# design.net
KiCad netlist of a schematic drawn in Altium Designer
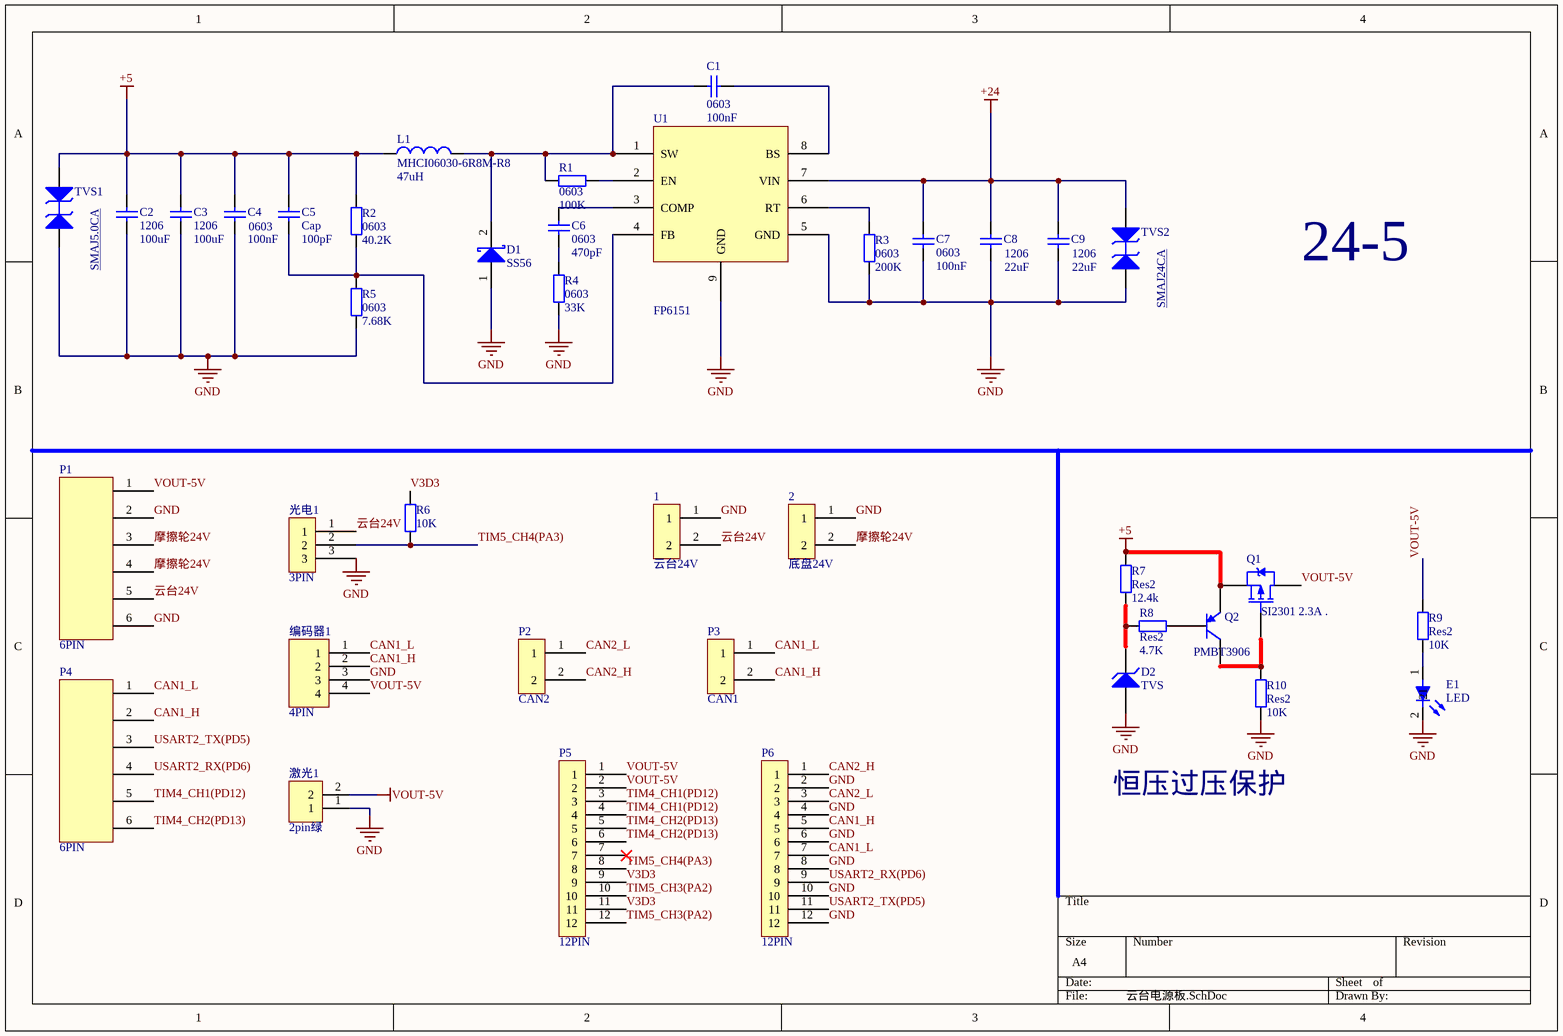
[diagram p0: 云台电源板.SchDoc]

(export (version "E")
  (design (tool "Eeschema 10.0.6"))
  (components
    (comp (ref "1") (value "云台24V") (footprint "XT30 pw") (libsource (lib "PP_SCHlib_Altium") (part "2PIN")))
    (comp (ref "2") (value "底盘24V") (footprint "XT30 pw") (libsource (lib "PP_SCHlib_Altium") (part "2PIN")))
    (comp (ref "C1")
      (value "0603")
      (footprint "C0603")
      (description "Capacitor")
      (fields (field (name "0603") "100nF") (field (name "PUBLISHER") "Altium Limited"))
      (libsource (lib "Miscellaneous Devices") (part "Cap"))
    )
    (comp (ref "C2")
      (value "1206")
      (footprint "C1206")
      (description "Capacitor")
      (fields (field (name "ALTIUM_VALUE") "100uF") (field (name "PUBLISHER") "Altium Limited"))
      (libsource (lib "Miscellaneous Devices") (part "Cap"))
    )
    (comp (ref "C3")
      (value "1206")
      (footprint "C1206")
      (description "Capacitor")
      (fields (field (name "ALTIUM_VALUE") "100uF") (field (name "PUBLISHER") "Altium Limited"))
      (libsource (lib "Miscellaneous Devices") (part "Cap"))
    )
    (comp (ref "C4")
      (value "0603")
      (footprint "C0603")
      (description "Capacitor")
      (fields (field (name "ALTIUM_VALUE") "100nF") (field (name "PUBLISHER") "Altium Limited"))
      (libsource (lib "Miscellaneous Devices") (part "Cap"))
    )
    (comp (ref "C5")
      (value "Cap")
      (footprint "C0603")
      (description "Capacitor")
      (fields (field (name "ALTIUM_VALUE") "100pF") (field (name "PUBLISHER") "Altium Limited"))
      (libsource (lib "Miscellaneous Devices") (part "Cap"))
    )
    (comp (ref "C6")
      (value "0603")
      (footprint "C0603")
      (description "Capacitor")
      (fields (field (name "ALTIUM_VALUE") "470pF") (field (name "PUBLISHER") "Altium Limited"))
      (libsource (lib "Miscellaneous Devices") (part "Cap"))
    )
    (comp (ref "C7")
      (value "0603")
      (footprint "C0603")
      (description "Capacitor")
      (fields (field (name "0603") "100nF") (field (name "PUBLISHER") "Altium Limited"))
      (libsource (lib "Miscellaneous Devices") (part "Cap"))
    )
    (comp (ref "C8")
      (value "1206")
      (footprint "C1206")
      (description "Capacitor")
      (fields (field (name "ALTIUM_VALUE") "22uF") (field (name "PUBLISHER") "Altium Limited"))
      (libsource (lib "Miscellaneous Devices") (part "Cap"))
    )
    (comp (ref "C9")
      (value "1206")
      (footprint "C1206")
      (description "Capacitor")
      (fields (field (name "ALTIUM_VALUE") "22uF") (field (name "PUBLISHER") "Altium Limited"))
      (libsource (lib "Miscellaneous Devices") (part "Cap"))
    )
    (comp (ref "D1")
      (value "D-Schottky")
      (footprint "SS56")
      (description "肖特基二极管")
      (fields (field (name "TYPE") "SS56") (field (name "PUBLISHER") "Altium Limited"))
      (libsource (lib "更多原理图库") (part "D-Schottky"))
    )
    (comp (ref "D2")
      (value "TVS")
      (footprint "SMA")
      (description "Zener Diode")
      (fields (field (name "PUBLISHER") "Altium Limited"))
      (libsource (lib "Miscellaneous Devices") (part "D Zener"))
    )
    (comp (ref "E1")
      (value "LED")
      (footprint "LED0805")
      (description "Typical RED, GREEN, YELLOW, AMBER GaAs LED")
      (fields (field (name "PUBLISHER") "Altium Limited"))
      (libsource (lib "PP_SCHlib_Altium") (part "LED"))
    )
    (comp (ref "L1")
      (value "MHCI06030-6R8M-R8")
      (footprint "L")
      (description "Inductor")
      (fields (field (name "ALTIUM_VALUE") "47uH") (field (name "PUBLISHER") "Altium Limited"))
      (libsource (lib "Miscellaneous Devices") (part "Inductor"))
    )
    (comp (ref "P1")
      (value "6PIN")
      (footprint "43045-6P-L")
      (libsource (lib "PP_SCHlib_Altium") (part "6PIN"))
    )
    (comp (ref "P2")
      (value "CAN2")
      (footprint "XH2.54-2-W")
      (libsource (lib "PP_SCHlib_Altium") (part "2PIN"))
    )
    (comp (ref "P3")
      (value "CAN1")
      (footprint "XH2.54-2-W")
      (libsource (lib "PP_SCHlib_Altium") (part "2PIN"))
    )
    (comp (ref "P4")
      (value "6PIN")
      (footprint "43045-6P-L")
      (libsource (lib "PP_SCHlib_Altium") (part "6PIN"))
    )
    (comp (ref "P5") (value "12PIN") (footprint "2mm-2-12") (libsource (lib "更多原理图库") (part "12PIN")))
    (comp (ref "P6") (value "12PIN") (footprint "2mm-2-12") (libsource (lib "更多原理图库") (part "12PIN")))
    (comp (ref "Q1")
      (value "SI2301 2.3A .")
      (footprint "SOT23")
      (description "P-Channel Power MOSFET")
      (fields (field (name "PUBLISHER") "Altium Limited"))
      (libsource (lib "Miscellaneous Devices") (part "PMOS-2"))
    )
    (comp (ref "Q2")
      (value "PMBT3906")
      (footprint "SOT23")
      (description "PNP Bipolar Transistor")
      (fields (field (name "PUBLISHER") "Altium Limited"))
      (libsource (lib "Miscellaneous Devices") (part "PNP"))
    )
    (comp (ref "R1")
      (value "0603")
      (footprint "R0603")
      (description "Resistor")
      (fields (field (name "0603") "100K") (field (name "PUBLISHER") "Altium Limited"))
      (libsource (lib "") (part "Res2_2"))
    )
    (comp (ref "R2")
      (value "0603")
      (footprint "R0603")
      (description "Resistor")
      (fields (field (name "ALTIUM_VALUE") "40.2K") (field (name "PUBLISHER") "Altium Limited"))
      (libsource (lib "Miscellaneous Devices") (part "Res2"))
    )
    (comp (ref "R3")
      (value "0603")
      (footprint "R0603")
      (description "Resistor")
      (fields (field (name "0603") "200K") (field (name "PUBLISHER") "Altium Limited"))
      (libsource (lib "Miscellaneous Devices") (part "Res2"))
    )
    (comp (ref "R4")
      (value "0603")
      (footprint "R0603")
      (description "Resistor")
      (fields (field (name "ALTIUM_VALUE") "33K") (field (name "PUBLISHER") "Altium Limited"))
      (libsource (lib "Miscellaneous Devices") (part "Res2"))
    )
    (comp (ref "R5")
      (value "0603")
      (footprint "R0603")
      (description "Resistor")
      (fields (field (name "ALTIUM_VALUE") "7.68K") (field (name "PUBLISHER") "Altium Limited"))
      (libsource (lib "Miscellaneous Devices") (part "Res2"))
    )
    (comp (ref "R6")
      (value "10K")
      (footprint "R0805")
      (description "贴片电阻")
      (fields (field (name "Comment") "Res1") (field (name "PUBLISHER") "Altium Limited"))
      (libsource (lib "stm32test") (part "Res1"))
    )
    (comp (ref "R7")
      (value "Res2")
      (footprint "0603(偏大)")
      (description "Resistor")
      (fields (field (name "ALTIUM_VALUE") "12.4k") (field (name "PUBLISHER") "Altium Limited"))
      (libsource (lib "Miscellaneous Devices") (part "Res2"))
    )
    (comp (ref "R8")
      (value "Res2")
      (footprint "0603(偏大)")
      (description "Resistor")
      (fields (field (name "ALTIUM_VALUE") "4.7K") (field (name "PUBLISHER") "Altium Limited"))
      (libsource (lib "") (part "Res2_1"))
    )
    (comp (ref "R9")
      (value "Res2")
      (footprint "0603(偏大)")
      (description "Resistor")
      (fields (field (name "ALTIUM_VALUE") "10K") (field (name "PUBLISHER") "Altium Limited"))
      (libsource (lib "") (part "Res2_3"))
    )
    (comp (ref "R10")
      (value "Res2")
      (footprint "0603(偏大)")
      (description "Resistor")
      (fields (field (name "ALTIUM_VALUE") "10K") (field (name "PUBLISHER") "Altium Limited"))
      (libsource (lib "Miscellaneous Devices") (part "Res2"))
    )
    (comp (ref "TVS1")
      (value "SMAJ5.0CA")
      (footprint "SMAJ")
      (libsource (lib "VL53L0X激光测距传感器模块") (part "TVS"))
    )
    (comp (ref "TVS2")
      (value "SMAJ24CA")
      (footprint "SMAJ")
      (libsource (lib "VL53L0X激光测距传感器模块") (part "TVS"))
    )
    (comp (ref "U1") (value "FP6151") (footprint "FP6151") (libsource (lib "Schlib1") (part "FP6151")))
    (comp (ref "光电1")
      (value "3PIN")
      (footprint "GH1.25 3PIN")
      (libsource (lib "PP_SCHlib_Altium") (part "3PIN"))
    )
    (comp (ref "激光1")
      (value "2pin绿")
      (footprint "532610271")
      (description "Molex-53261-0871")
      (fields (field (name "PUBLISHER") "Altium Limited"))
      (libsource (lib "通用板") (part "Molex-53398-0271"))
    )
    (comp (ref "编码器1")
      (value "4PIN")
      (footprint "XH2.54-4-w")
      (libsource (lib "PP_SCHlib_Altium") (part "4PIN"))
    )
  )
  (nets
    (net (code "1") (name "+5") (class "Default")
      (node (ref "C2") (pin "2") (pinfunction "2_2") (pintype "passive"))
      (node (ref "C3") (pin "2") (pinfunction "2_2") (pintype "passive"))
      (node (ref "C4") (pin "2") (pinfunction "2_2") (pintype "passive"))
      (node (ref "C5") (pin "2") (pinfunction "2_2") (pintype "passive"))
      (node (ref "L1") (pin "1") (pinfunction "1_1") (pintype "passive"))
      (node (ref "Q1") (pin "2") (pinfunction "s_2") (pintype "passive"))
      (node (ref "Q2") (pin "2") (pinfunction "2_2") (pintype "passive"))
      (node (ref "R2") (pin "2") (pinfunction "2_2") (pintype "passive"))
      (node (ref "R7") (pin "2") (pinfunction "2_2") (pintype "passive"))
      (node (ref "TVS1") (pin "2") (pinfunction "K_2") (pintype "passive"))
    )
    (net (code "2") (name "+24") (class "Default")
      (node (ref "C7") (pin "2") (pinfunction "2_2") (pintype "passive"))
      (node (ref "C8") (pin "2") (pinfunction "2_2") (pintype "passive"))
      (node (ref "C9") (pin "2") (pinfunction "2_2") (pintype "passive"))
      (node (ref "TVS2") (pin "2") (pinfunction "K_2") (pintype "passive"))
      (node (ref "U1") (pin "7") (pinfunction "VIN_7") (pintype "passive"))
    )
    (net (code "3") (name "/CAN1_H") (class "Default")
      (node (ref "P3") (pin "2") (pinfunction "2_2") (pintype "passive"))
      (node (ref "P4") (pin "2") (pinfunction "2_2") (pintype "passive"))
      (node (ref "P6") (pin "5") (pinfunction "5_5") (pintype "passive"))
      (node (ref "编码器1") (pin "2") (pinfunction "2_2") (pintype "passive"))
    )
    (net (code "4") (name "/CAN1_L") (class "Default")
      (node (ref "P3") (pin "1") (pinfunction "1_1") (pintype "passive"))
      (node (ref "P4") (pin "1") (pinfunction "1_1") (pintype "passive"))
      (node (ref "P6") (pin "7") (pinfunction "7_7") (pintype "passive"))
      (node (ref "编码器1") (pin "1") (pinfunction "1_1") (pintype "passive"))
    )
    (net (code "5") (name "/CAN2_H") (class "Default")
      (node (ref "P2") (pin "2") (pinfunction "2_2") (pintype "passive"))
      (node (ref "P6") (pin "1") (pinfunction "1_1") (pintype "passive"))
    )
    (net (code "6") (name "/CAN2_L") (class "Default")
      (node (ref "P2") (pin "1") (pinfunction "1_1") (pintype "passive"))
      (node (ref "P6") (pin "3") (pinfunction "3_3") (pintype "passive"))
    )
    (net (code "7") (name "/TIM4_CH1(PD12)") (class "Default")
      (node (ref "P4") (pin "5") (pinfunction "5_5") (pintype "passive"))
      (node (ref "P5") (pin "3") (pinfunction "3_3") (pintype "passive"))
      (node (ref "P5") (pin "4") (pinfunction "4_4") (pintype "passive"))
    )
    (net (code "8") (name "/TIM4_CH2(PD13)") (class "Default")
      (node (ref "P4") (pin "6") (pinfunction "6_6") (pintype "passive"))
      (node (ref "P5") (pin "5") (pinfunction "5_5") (pintype "passive"))
      (node (ref "P5") (pin "6") (pinfunction "6_6") (pintype "passive"))
    )
    (net (code "9") (name "/TIM5_CH3(PA2)") (class "Default")
      (node (ref "P5") (pin "10") (pinfunction "10_10") (pintype "passive"))
      (node (ref "P5") (pin "12") (pinfunction "12_12") (pintype "passive"))
    )
    (net (code "10") (name "/TIM5_CH4(PA3)") (class "Default")
      (node (ref "P5") (pin "8") (pinfunction "8_8") (pintype "passive"))
      (node (ref "R6") (pin "1") (pinfunction "1_1") (pintype "passive"))
      (node (ref "光电1") (pin "2") (pinfunction "2_2") (pintype "passive"))
    )
    (net (code "11") (name "/USART2_RX(PD6)") (class "Default")
      (node (ref "P4") (pin "4") (pinfunction "4_4") (pintype "passive"))
      (node (ref "P6") (pin "9") (pinfunction "9_9") (pintype "passive"))
    )
    (net (code "12") (name "/USART2_TX(PD5)") (class "Default")
      (node (ref "P4") (pin "3") (pinfunction "3_3") (pintype "passive"))
      (node (ref "P6") (pin "11") (pinfunction "11_11") (pintype "passive"))
    )
    (net (code "13") (name "/V3D3") (class "Default")
      (node (ref "P5") (pin "11") (pinfunction "11_11") (pintype "passive"))
      (node (ref "P5") (pin "9") (pinfunction "9_9") (pintype "passive"))
      (node (ref "R6") (pin "2") (pinfunction "2_2") (pintype "passive"))
    )
    (net (code "14") (name "/云台24V") (class "Default")
      (node (ref "1") (pin "2") (pinfunction "2_2") (pintype "passive"))
      (node (ref "P1") (pin "5") (pinfunction "5_5") (pintype "passive"))
      (node (ref "光电1") (pin "1") (pinfunction "1_1") (pintype "passive"))
    )
    (net (code "15") (name "/摩擦轮24V") (class "Default")
      (node (ref "2") (pin "2") (pinfunction "2_2") (pintype "passive"))
      (node (ref "P1") (pin "3") (pinfunction "3_3") (pintype "passive"))
      (node (ref "P1") (pin "4") (pinfunction "4_4") (pintype "passive"))
    )
    (net (code "16") (name "GND") (class "Default")
      (node (ref "1") (pin "1") (pinfunction "1_1") (pintype "passive"))
      (node (ref "2") (pin "1") (pinfunction "1_1") (pintype "passive"))
      (node (ref "C2") (pin "1") (pinfunction "1_1") (pintype "passive"))
      (node (ref "C3") (pin "1") (pinfunction "1_1") (pintype "passive"))
      (node (ref "C4") (pin "1") (pinfunction "1_1") (pintype "passive"))
      (node (ref "C7") (pin "1") (pinfunction "1_1") (pintype "passive"))
      (node (ref "C8") (pin "1") (pinfunction "1_1") (pintype "passive"))
      (node (ref "C9") (pin "1") (pinfunction "1_1") (pintype "passive"))
      (node (ref "D1") (pin "1") (pinfunction "A_1") (pintype "passive"))
      (node (ref "D2") (pin "1") (pinfunction "A_1") (pintype "passive"))
      (node (ref "E1") (pin "2") (pinfunction "2_2") (pintype "passive"))
      (node (ref "P1") (pin "2") (pinfunction "2_2") (pintype "passive"))
      (node (ref "P1") (pin "6") (pinfunction "6_6") (pintype "passive"))
      (node (ref "P6") (pin "10") (pinfunction "10_10") (pintype "passive"))
      (node (ref "P6") (pin "12") (pinfunction "12_12") (pintype "passive"))
      (node (ref "P6") (pin "2") (pinfunction "2_2") (pintype "passive"))
      (node (ref "P6") (pin "4") (pinfunction "4_4") (pintype "passive"))
      (node (ref "P6") (pin "6") (pinfunction "6_6") (pintype "passive"))
      (node (ref "P6") (pin "8") (pinfunction "8_8") (pintype "passive"))
      (node (ref "R10") (pin "1") (pinfunction "1_1") (pintype "passive"))
      (node (ref "R3") (pin "1") (pinfunction "1_1") (pintype "passive"))
      (node (ref "R4") (pin "1") (pinfunction "1_1") (pintype "passive"))
      (node (ref "R5") (pin "1") (pinfunction "1_1") (pintype "passive"))
      (node (ref "TVS1") (pin "1") (pinfunction "A_1") (pintype "passive"))
      (node (ref "TVS2") (pin "1") (pinfunction "A_1") (pintype "passive"))
      (node (ref "U1") (pin "5") (pinfunction "GND_5") (pintype "passive"))
      (node (ref "U1") (pin "9") (pinfunction "GND_9") (pintype "passive"))
      (node (ref "光电1") (pin "3") (pinfunction "3_3") (pintype "passive"))
      (node (ref "激光1") (pin "1") (pinfunction "1_1") (pintype "passive"))
      (node (ref "编码器1") (pin "3") (pinfunction "3_3") (pintype "passive"))
    )
    (net (code "17") (name "Net-(C6-Pad1)") (class "Default")
      (node (ref "C6") (pin "1") (pinfunction "1_1") (pintype "passive"))
      (node (ref "R4") (pin "2") (pinfunction "2_2") (pintype "passive"))
    )
    (net (code "18") (name "Net-(D1-K)") (class "Default")
      (node (ref "C1") (pin "2") (pinfunction "2_2") (pintype "passive"))
      (node (ref "D1") (pin "2") (pinfunction "K_2") (pintype "passive"))
      (node (ref "L1") (pin "2") (pinfunction "2_2") (pintype "passive"))
      (node (ref "R1") (pin "2") (pinfunction "2_2") (pintype "passive"))
      (node (ref "U1") (pin "1") (pinfunction "SW_1") (pintype "passive"))
    )
    (net (code "19") (name "Net-(D2-K)") (class "Default")
      (node (ref "D2") (pin "2") (pinfunction "K_2") (pintype "passive"))
      (node (ref "R7") (pin "1") (pinfunction "1_1") (pintype "passive"))
      (node (ref "R8") (pin "1") (pinfunction "1_1") (pintype "passive"))
    )
    (net (code "20") (name "Net-(E1-Pad1)") (class "Default")
      (node (ref "E1") (pin "1") (pinfunction "1_1") (pintype "passive"))
      (node (ref "R9") (pin "2") (pinfunction "2_2") (pintype "passive"))
    )
    (net (code "21") (name "Net-(Q1-G)") (class "Default")
      (node (ref "Q1") (pin "1") (pinfunction "G_1") (pintype "passive"))
      (node (ref "Q2") (pin "3") (pinfunction "3_3") (pintype "passive"))
      (node (ref "R10") (pin "2") (pinfunction "2_2") (pintype "passive"))
    )
    (net (code "22") (name "Net-(Q2-Pad1)") (class "Default")
      (node (ref "Q2") (pin "1") (pinfunction "1_1") (pintype "passive"))
      (node (ref "R8") (pin "2") (pinfunction "2_2") (pintype "passive"))
    )
    (net (code "23") (name "Net-(U1-BS)") (class "Default")
      (node (ref "C1") (pin "1") (pinfunction "1_1") (pintype "passive"))
      (node (ref "U1") (pin "8") (pinfunction "BS_8") (pintype "passive"))
    )
    (net (code "24") (name "Net-(U1-COMP)") (class "Default")
      (node (ref "C6") (pin "2") (pinfunction "2_2") (pintype "passive"))
      (node (ref "U1") (pin "3") (pinfunction "COMP_3") (pintype "passive"))
    )
    (net (code "25") (name "Net-(U1-EN)") (class "Default")
      (node (ref "R1") (pin "1") (pinfunction "1_1") (pintype "passive"))
      (node (ref "U1") (pin "2") (pinfunction "EN_2") (pintype "passive"))
    )
    (net (code "26") (name "Net-(U1-FB)") (class "Default")
      (node (ref "C5") (pin "1") (pinfunction "1_1") (pintype "passive"))
      (node (ref "R2") (pin "1") (pinfunction "1_1") (pintype "passive"))
      (node (ref "R5") (pin "2") (pinfunction "2_2") (pintype "passive"))
      (node (ref "U1") (pin "4") (pinfunction "FB_4") (pintype "passive"))
    )
    (net (code "27") (name "Net-(U1-RT)") (class "Default")
      (node (ref "R3") (pin "2") (pinfunction "2_2") (pintype "passive"))
      (node (ref "U1") (pin "6") (pinfunction "RT_6") (pintype "passive"))
    )
    (net (code "28") (name "VOUT-5V") (class "Default")
      (node (ref "P1") (pin "1") (pinfunction "1_1") (pintype "passive"))
      (node (ref "P5") (pin "1") (pinfunction "1_1") (pintype "passive"))
      (node (ref "P5") (pin "2") (pinfunction "2_2") (pintype "passive"))
      (node (ref "Q1") (pin "3") (pinfunction "D_3") (pintype "passive"))
      (node (ref "R9") (pin "1") (pinfunction "1_1") (pintype "passive"))
      (node (ref "激光1") (pin "2") (pinfunction "2_2") (pintype "passive"))
      (node (ref "编码器1") (pin "4") (pinfunction "4_4") (pintype "passive"))
    )
    (net (code "29") (name "unconnected-(P5-Pad7)") (class "Default")
      (node (ref "P5") (pin "7") (pinfunction "7_7") (pintype "passive+no_connect"))
    )
  )
)
